# untitled.net
KiCad netlist of a schematic drawn in EAGLE
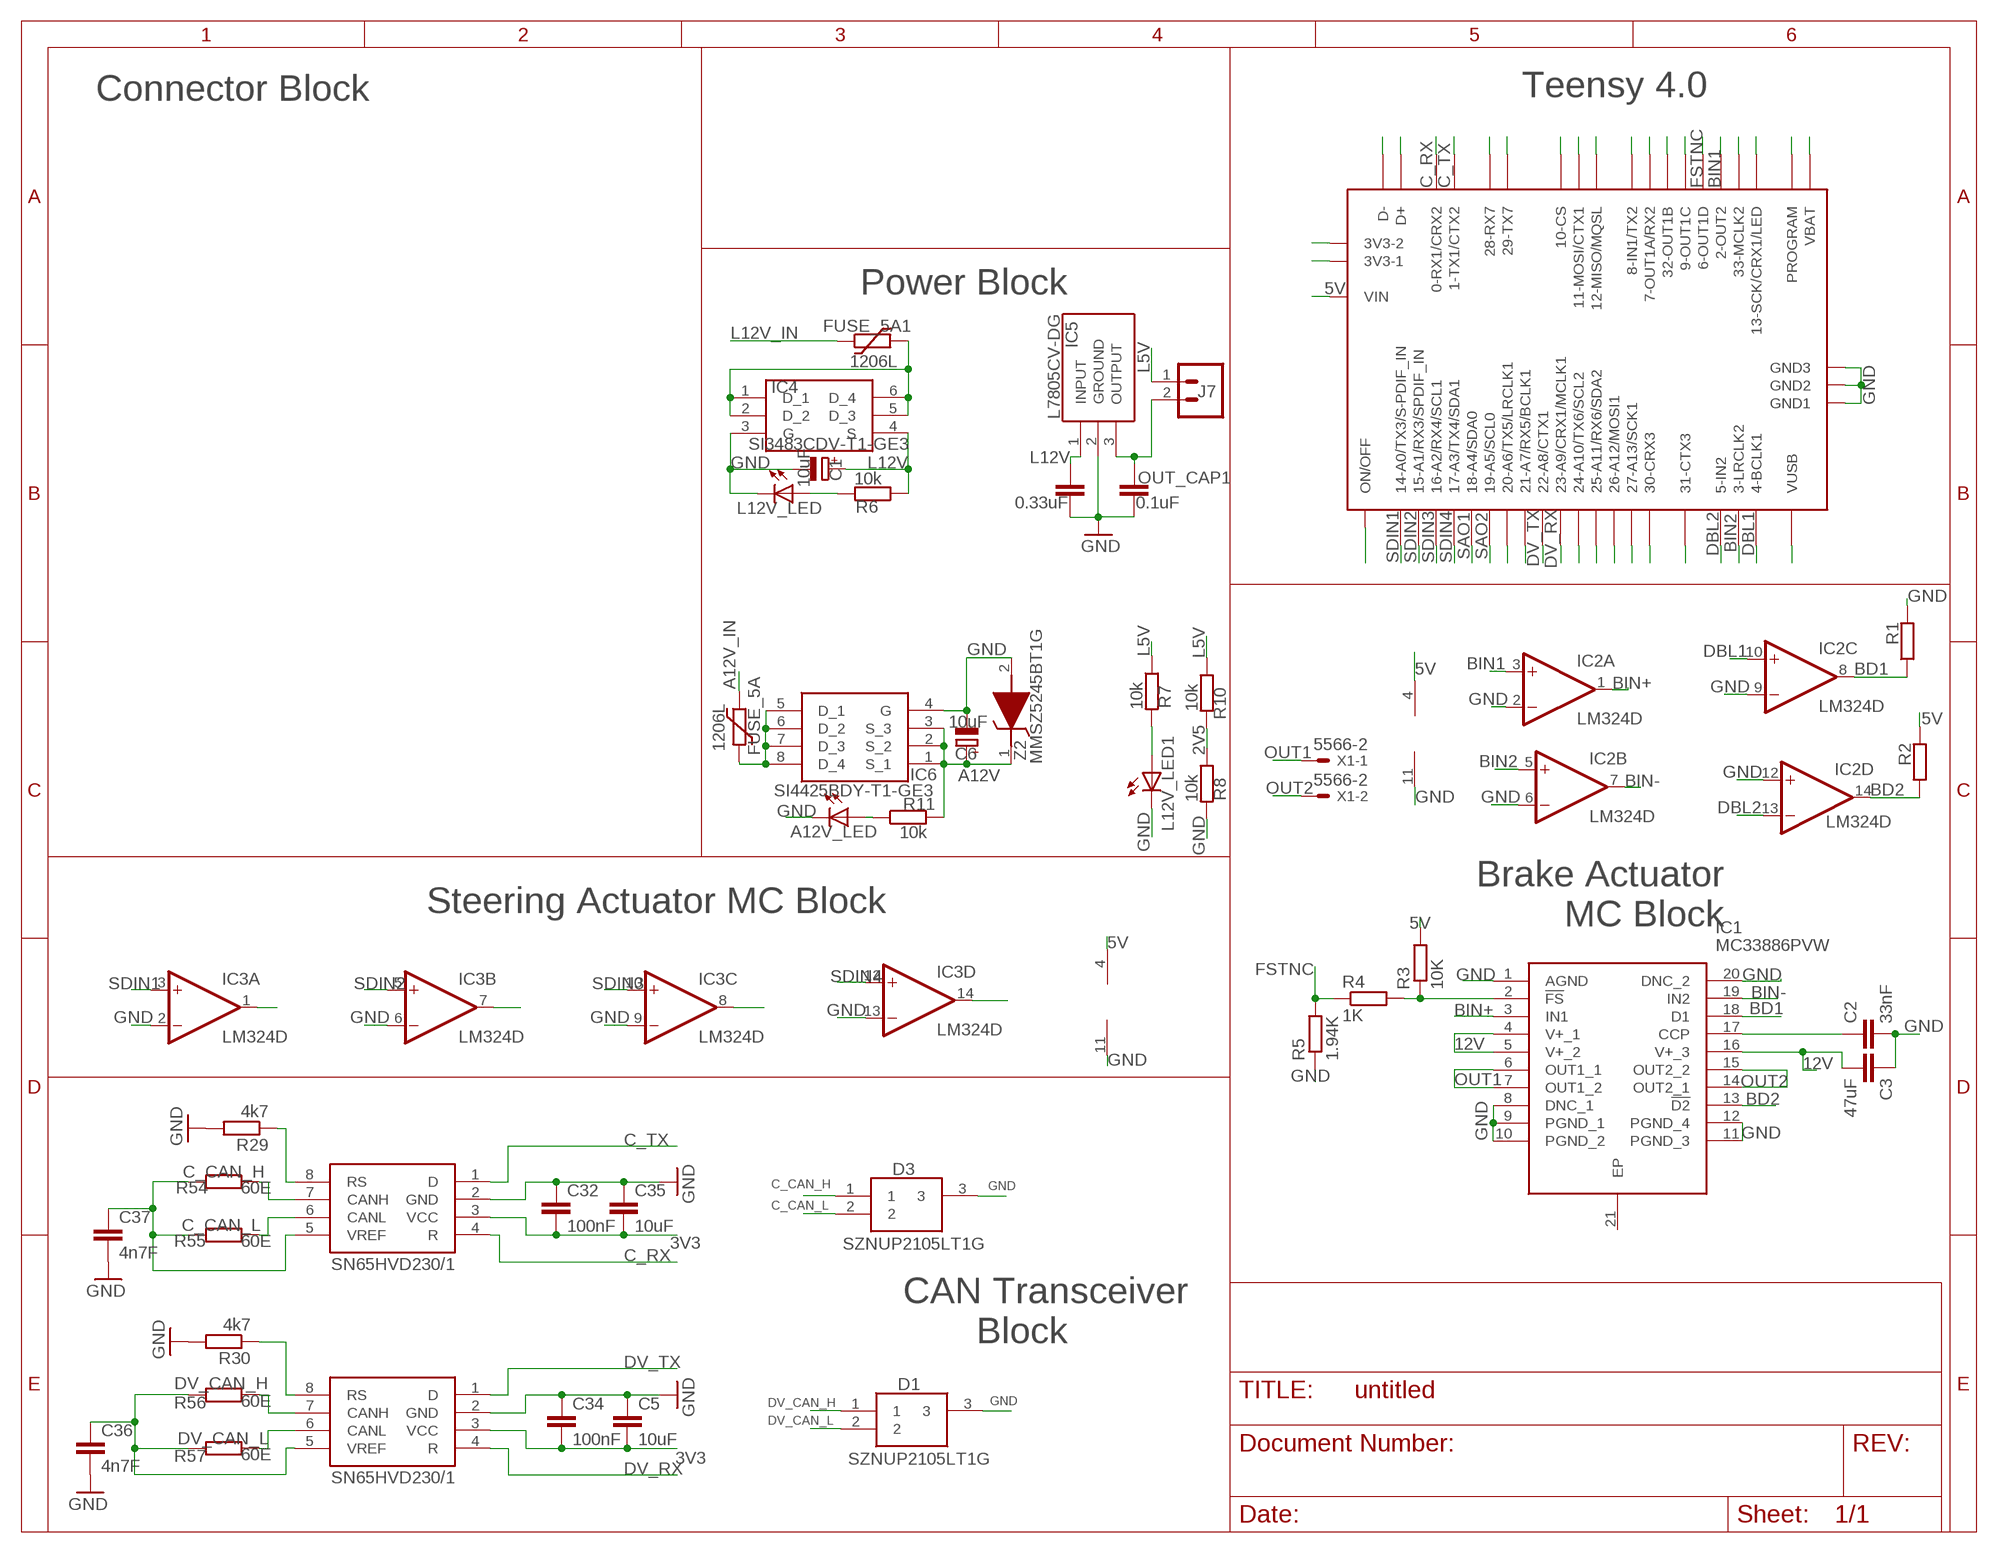
[diagram p0: schematic, sheet 1]

(export (version "E")
  (design (tool "Eeschema 10.0.6"))
  (components
    (comp (ref "A12V_LED")
      (value "LED1206")
      (footprint "eagle-import:LED-1206")
      (libsource (lib "eagle-import") (part "LED1206"))
    )
    (comp (ref "C1")
      (value "10uF")
      (footprint "eagle-import:E2,5-6")
      (libsource (lib "eagle-import") (part "CPOL-EUE2.5-6"))
    )
    (comp (ref "C2")
      (value "33nF")
      (footprint "eagle-import:C0805")
      (libsource (lib "eagle-import") (part "rcl_334_C-EUC0805"))
    )
    (comp (ref "C3")
      (value "47uF")
      (footprint "eagle-import:C1206")
      (libsource (lib "eagle-import") (part "rcl_334_C-EUC1206"))
    )
    (comp (ref "C5")
      (value "10uF")
      (footprint "eagle-import:C0805")
      (libsource (lib "eagle-import") (part "C-EUC0805"))
    )
    (comp (ref "C6")
      (value "10uF")
      (footprint "eagle-import:E2,5-6")
      (libsource (lib "eagle-import") (part "CPOL-EUE2.5-6"))
    )
    (comp (ref "C32")
      (value "100nF")
      (footprint "eagle-import:C0805")
      (libsource (lib "eagle-import") (part "C-EUC0805"))
    )
    (comp (ref "C34")
      (value "100nF")
      (footprint "eagle-import:C0805")
      (libsource (lib "eagle-import") (part "C-EUC0805"))
    )
    (comp (ref "C35")
      (value "10uF")
      (footprint "eagle-import:C0805")
      (libsource (lib "eagle-import") (part "C-EUC0805"))
    )
    (comp (ref "C36")
      (value "4n7F")
      (footprint "eagle-import:C0805")
      (libsource (lib "eagle-import") (part "C-EUC0805"))
    )
    (comp (ref "C37")
      (value "4n7F")
      (footprint "eagle-import:C0805")
      (libsource (lib "eagle-import") (part "C-EUC0805"))
    )
    (comp (ref "D1")
      (value "SZNUP2105LT1G")
      (footprint "eagle-import:SOT96P237X111-3N")
      (fields (field (name "MOUSER_PART_NUMBER") "863-SZNUP2105LT1G"))
      (libsource (lib "eagle-import") (part "SZNUP2105LT1G"))
    )
    (comp (ref "D3")
      (value "SZNUP2105LT1G")
      (footprint "eagle-import:SOT96P237X111-3N")
      (fields (field (name "MOUSER_PART_NUMBER") "863-SZNUP2105LT1G"))
      (libsource (lib "eagle-import") (part "SZNUP2105LT1G"))
    )
    (comp (ref "FUSE_5A")
      (value "1206L")
      (footprint "eagle-import:1206L")
      (libsource (lib "eagle-import") (part "1206L"))
    )
    (comp (ref "FUSE_5A1")
      (value "1206L")
      (footprint "eagle-import:1206L")
      (libsource (lib "eagle-import") (part "1206L"))
    )
    (comp (ref "IC1")
      (value "MC33886PVW")
      (footprint "eagle-import:SOIC127P1420X340-21N")
      (fields (field (name "MOUSER_PART_NUMBER") "841-MC33886PVW"))
      (libsource (lib "eagle-import") (part "MC33886PVW"))
    )
    (comp (ref "IC2")
      (value "LM324D")
      (footprint "eagle-import:SO14")
      (libsource (lib "eagle-import") (part "LM324D"))
    )
    (comp (ref "IC3")
      (value "LM324D")
      (footprint "eagle-import:SO14")
      (libsource (lib "eagle-import") (part "LM324D"))
    )
    (comp (ref "IC4")
      (value "SI3483CDV-T1-GE3")
      (footprint "eagle-import:SOP95P284X110-6N")
      (fields (field (name "MOUSER_PART_NUMBER") "781-SI3483CDV-GE3"))
      (libsource (lib "eagle-import") (part "SI3483CDV-T1-GE3"))
    )
    (comp (ref "IC5")
      (value "L7805CV-DG")
      (footprint "eagle-import:TO255P460X1020X2008-3P")
      (fields (field (name "MOUSER_PART_NUMBER") "511-L7805CV-DG"))
      (libsource (lib "eagle-import") (part "L7805CV-DG"))
    )
    (comp (ref "IC6")
      (value "SI4425BDY-T1-GE3")
      (footprint "eagle-import:SOIC127P600X175-8N")
      (fields (field (name "MOUSER_PART_NUMBER") "781-SI4425BDY-GE3"))
      (libsource (lib "eagle-import") (part "SI4425BDY-T1-GE3"))
    )
    (comp (ref "IN_CAP1")
      (value "0.33uF")
      (footprint "eagle-import:C0805")
      (libsource (lib "eagle-import") (part "C-EUC0805"))
    )
    (comp (ref "J7")
      (value "CONN_02")
      (footprint "eagle-import:1X02")
      (libsource (lib "eagle-import") (part "CONN_02"))
    )
    (comp (ref "L12V_LED")
      (value "LED1206")
      (footprint "eagle-import:LED-1206")
      (libsource (lib "eagle-import") (part "LED1206"))
    )
    (comp (ref "L12V_LED1")
      (value "LED1206")
      (footprint "eagle-import:LED-1206")
      (libsource (lib "eagle-import") (part "LED1206"))
    )
    (comp (ref "OUT_CAP1")
      (value "0.1uF")
      (footprint "eagle-import:C0805")
      (libsource (lib "eagle-import") (part "C-EUC0805"))
    )
    (comp (ref "R1")
      (value "R-EU_R0805")
      (footprint "eagle-import:R0805")
      (libsource (lib "eagle-import") (part "rcl_334_R-EU_R0805"))
    )
    (comp (ref "R2")
      (value "R-EU_R0805")
      (footprint "eagle-import:R0805")
      (libsource (lib "eagle-import") (part "rcl_334_R-EU_R0805"))
    )
    (comp (ref "R3")
      (value "10K")
      (footprint "eagle-import:R0805")
      (libsource (lib "eagle-import") (part "rcl_334_R-EU_R0805"))
    )
    (comp (ref "R4")
      (value "1K")
      (footprint "eagle-import:R0805")
      (libsource (lib "eagle-import") (part "rcl_334_R-EU_R0805"))
    )
    (comp (ref "R5")
      (value "1.94K")
      (footprint "eagle-import:R0805")
      (libsource (lib "eagle-import") (part "rcl_334_R-EU_R0805"))
    )
    (comp (ref "R6")
      (value "10k")
      (footprint "eagle-import:R0805")
      (libsource (lib "eagle-import") (part "R-EU_R0805"))
    )
    (comp (ref "R7")
      (value "10k")
      (footprint "eagle-import:R0805")
      (libsource (lib "eagle-import") (part "R-EU_R0805"))
    )
    (comp (ref "R8")
      (value "10k")
      (footprint "eagle-import:R0805")
      (libsource (lib "eagle-import") (part "R-EU_R0805"))
    )
    (comp (ref "R10")
      (value "10k")
      (footprint "eagle-import:R0805")
      (libsource (lib "eagle-import") (part "R-EU_R0805"))
    )
    (comp (ref "R11")
      (value "10k")
      (footprint "eagle-import:R0805")
      (libsource (lib "eagle-import") (part "R-EU_R0805"))
    )
    (comp (ref "R29")
      (value "4k7")
      (footprint "eagle-import:R0805")
      (libsource (lib "eagle-import") (part "R-EU_R0805"))
    )
    (comp (ref "R30")
      (value "4k7")
      (footprint "eagle-import:R0805")
      (libsource (lib "eagle-import") (part "R-EU_R0805"))
    )
    (comp (ref "R54")
      (value "60E")
      (footprint "eagle-import:R0805")
      (libsource (lib "eagle-import") (part "R-EU_R0805"))
    )
    (comp (ref "R55")
      (value "60E")
      (footprint "eagle-import:R0805")
      (libsource (lib "eagle-import") (part "R-EU_R0805"))
    )
    (comp (ref "R56")
      (value "60E")
      (footprint "eagle-import:R0805")
      (libsource (lib "eagle-import") (part "R-EU_R0805"))
    )
    (comp (ref "R57")
      (value "60E")
      (footprint "eagle-import:R0805")
      (libsource (lib "eagle-import") (part "R-EU_R0805"))
    )
    (comp (ref "U$1")
      (value "TEENSY40")
      (footprint "eagle-import:TEENSY40")
      (libsource (lib "eagle-import") (part "TEENSY40"))
    )
    (comp (ref "U$7")
      (value "SN65HVD230/1")
      (footprint "eagle-import:SO8")
      (libsource (lib "eagle-import") (part "SN65HVD230/1"))
    )
    (comp (ref "U$8")
      (value "SN65HVD230/1")
      (footprint "eagle-import:SO8")
      (libsource (lib "eagle-import") (part "SN65HVD230/1"))
    )
    (comp (ref "X1")
      (value "5566-2")
      (footprint "eagle-import:5566-2")
      (fields (field (name "MF") "MOLEX"))
      (libsource (lib "eagle-import") (part "5566-2"))
    )
    (comp (ref "Z2")
      (value "MMSZ5245BT1G")
      (footprint "eagle-import:SOD3716X135N")
      (fields (field (name "MOUSER_PART_NUMBER") "863-MMSZ5245BT1G"))
      (libsource (lib "eagle-import") (part "MMSZ5245BT1G"))
    )
  )
  (nets
    (net (code "1") (name "/2V5") (class "Default")
      (node (ref "R10") (pin "2") (pinfunction "2_2") (pintype "passive"))
      (node (ref "R8") (pin "1") (pinfunction "1_1") (pintype "passive"))
    )
    (net (code "2") (name "/3V3") (class "Default")
      (node (ref "C32") (pin "2") (pinfunction "2_2") (pintype "passive"))
      (node (ref "C34") (pin "2") (pinfunction "2_2") (pintype "passive"))
      (node (ref "C35") (pin "2") (pinfunction "2_2") (pintype "passive"))
      (node (ref "C5") (pin "2") (pinfunction "2_2") (pintype "passive"))
      (node (ref "U$7") (pin "3") (pinfunction "VCC_3") (pintype "power_in"))
      (node (ref "U$8") (pin "3") (pinfunction "VCC_3") (pintype "power_in"))
    )
    (net (code "3") (name "/5V") (class "Default")
      (node (ref "IC2") (pin "4") (pinfunction "V+_4") (pintype "power_in"))
      (node (ref "IC3") (pin "4") (pinfunction "V+_4") (pintype "power_in"))
      (node (ref "R2") (pin "2") (pinfunction "2_2") (pintype "passive"))
      (node (ref "R3") (pin "2") (pinfunction "2_2") (pintype "passive"))
      (node (ref "U$1") (pin "VIN") (pinfunction "VIN_VIN") (pintype "bidirectional"))
    )
    (net (code "4") (name "/12V") (class "Default")
      (node (ref "C3") (pin "2") (pinfunction "2_2") (pintype "passive"))
      (node (ref "IC1") (pin "16") (pinfunction "V+_3_16") (pintype "bidirectional"))
      (node (ref "IC1") (pin "4") (pinfunction "V+_1_4") (pintype "bidirectional"))
      (node (ref "IC1") (pin "5") (pinfunction "V+_2_5") (pintype "bidirectional"))
    )
    (net (code "5") (name "/A12V") (class "Default")
      (node (ref "C6") (pin "+") (pinfunction "+_+") (pintype "passive"))
      (node (ref "IC6") (pin "1") (pinfunction "S_1_1") (pintype "bidirectional"))
      (node (ref "IC6") (pin "2") (pinfunction "S_2_2") (pintype "bidirectional"))
      (node (ref "IC6") (pin "3") (pinfunction "S_3_3") (pintype "bidirectional"))
      (node (ref "R11") (pin "2") (pinfunction "2_2") (pintype "passive"))
      (node (ref "Z2") (pin "1") (pinfunction "K_1") (pintype "bidirectional"))
    )
    (net (code "6") (name "/A12V_IN") (class "Default")
      (node (ref "FUSE_5A") (pin "P$1") (pinfunction "1_P$1") (pintype "passive"))
    )
    (net (code "7") (name "/BD1") (class "Default")
      (node (ref "IC1") (pin "18") (pinfunction "D1_18") (pintype "bidirectional"))
      (node (ref "IC2") (pin "8") (pinfunction "OUT_8") (pintype "output"))
      (node (ref "R1") (pin "1") (pinfunction "1_1") (pintype "passive"))
    )
    (net (code "8") (name "/BD2") (class "Default")
      (node (ref "IC1") (pin "13") (pinfunction "~{D2}_13") (pintype "bidirectional"))
      (node (ref "IC2") (pin "14") (pinfunction "OUT_14") (pintype "output"))
      (node (ref "R2") (pin "1") (pinfunction "1_1") (pintype "passive"))
    )
    (net (code "9") (name "/BIN+") (class "Default")
      (node (ref "IC1") (pin "3") (pinfunction "IN1_3") (pintype "bidirectional"))
      (node (ref "IC2") (pin "1") (pinfunction "OUT_1") (pintype "output"))
    )
    (net (code "10") (name "/BIN-") (class "Default")
      (node (ref "IC1") (pin "19") (pinfunction "IN2_19") (pintype "bidirectional"))
      (node (ref "IC2") (pin "7") (pinfunction "OUT_7") (pintype "output"))
    )
    (net (code "11") (name "/BIN1") (class "Default")
      (node (ref "IC2") (pin "3") (pinfunction "+IN_3") (pintype "input"))
      (node (ref "U$1") (pin "2-OUT2") (pinfunction "2-OUT2_2-OUT2") (pintype "bidirectional"))
    )
    (net (code "12") (name "/BIN2") (class "Default")
      (node (ref "IC2") (pin "5") (pinfunction "+IN_5") (pintype "input"))
      (node (ref "U$1") (pin "3-LRCLK2") (pinfunction "3-LRCLK2_3-LRCLK2") (pintype "bidirectional"))
    )
    (net (code "13") (name "/C_CAN_H") (class "Default")
      (node (ref "D3") (pin "1") (pinfunction "1_1") (pintype "bidirectional"))
      (node (ref "R54") (pin "1") (pinfunction "1_1") (pintype "passive"))
      (node (ref "U$8") (pin "7") (pinfunction "CANH_7") (pintype "bidirectional"))
    )
    (net (code "14") (name "/C_CAN_L") (class "Default")
      (node (ref "D3") (pin "2") (pinfunction "2_2") (pintype "bidirectional"))
      (node (ref "R55") (pin "1") (pinfunction "1_1") (pintype "passive"))
      (node (ref "U$8") (pin "6") (pinfunction "CANL_6") (pintype "bidirectional"))
    )
    (net (code "15") (name "/C_RX") (class "Default")
      (node (ref "U$1") (pin "0-RX1") (pinfunction "0-RX1/CRX2_0-RX1") (pintype "bidirectional"))
      (node (ref "U$8") (pin "4") (pinfunction "R_4") (pintype "bidirectional"))
    )
    (net (code "16") (name "/C_TX") (class "Default")
      (node (ref "U$1") (pin "1-TX1") (pinfunction "1-TX1/CTX2_1-TX1") (pintype "bidirectional"))
      (node (ref "U$8") (pin "1") (pinfunction "D_1") (pintype "bidirectional"))
    )
    (net (code "17") (name "/DBL1") (class "Default")
      (node (ref "IC2") (pin "10") (pinfunction "+IN_10") (pintype "input"))
      (node (ref "U$1") (pin "4-BCLK2") (pinfunction "4-BCLK1_4-BCLK2") (pintype "bidirectional"))
    )
    (net (code "18") (name "/DBL2") (class "Default")
      (node (ref "IC2") (pin "13") (pinfunction "-IN_13") (pintype "input"))
      (node (ref "U$1") (pin "5-IN2") (pinfunction "5-IN2_5-IN2") (pintype "bidirectional"))
    )
    (net (code "19") (name "/DV_CAN_H") (class "Default")
      (node (ref "D1") (pin "1") (pinfunction "1_1") (pintype "bidirectional"))
      (node (ref "R56") (pin "1") (pinfunction "1_1") (pintype "passive"))
      (node (ref "U$7") (pin "7") (pinfunction "CANH_7") (pintype "bidirectional"))
    )
    (net (code "20") (name "/DV_CAN_L") (class "Default")
      (node (ref "D1") (pin "2") (pinfunction "2_2") (pintype "bidirectional"))
      (node (ref "R57") (pin "1") (pinfunction "1_1") (pintype "passive"))
      (node (ref "U$7") (pin "6") (pinfunction "CANL_6") (pintype "bidirectional"))
    )
    (net (code "21") (name "/DV_RX") (class "Default")
      (node (ref "U$1") (pin "23-A9/CRX1/CCLK1") (pinfunction "23-A9/CRX1/MCLK1_23-A9/CRX1/CCLK1") (pintype "bidirectional"))
      (node (ref "U$7") (pin "4") (pinfunction "R_4") (pintype "bidirectional"))
    )
    (net (code "22") (name "/DV_TX") (class "Default")
      (node (ref "U$1") (pin "22-A8/CTX1") (pinfunction "22-A8/CTX1_22-A8/CTX1") (pintype "bidirectional"))
      (node (ref "U$7") (pin "1") (pinfunction "D_1") (pintype "bidirectional"))
    )
    (net (code "23") (name "/FSTNC") (class "Default")
      (node (ref "R4") (pin "1") (pinfunction "1_1") (pintype "passive"))
      (node (ref "R5") (pin "2") (pinfunction "2_2") (pintype "passive"))
      (node (ref "U$1") (pin "6-OUT1D") (pinfunction "6-OUT1D_6-OUT1D") (pintype "bidirectional"))
    )
    (net (code "24") (name "/L5V") (class "Default")
      (node (ref "J7") (pin "1") (pinfunction "1_1") (pintype "passive"))
      (node (ref "R10") (pin "1") (pinfunction "1_1") (pintype "passive"))
      (node (ref "R7") (pin "1") (pinfunction "1_1") (pintype "passive"))
    )
    (net (code "25") (name "/L12V") (class "Default")
      (node (ref "C1") (pin "+") (pinfunction "+_+") (pintype "passive"))
      (node (ref "IC4") (pin "4") (pinfunction "S_4") (pintype "bidirectional"))
      (node (ref "IC5") (pin "1") (pinfunction "INPUT_1") (pintype "bidirectional"))
      (node (ref "IN_CAP1") (pin "1") (pinfunction "1_1") (pintype "passive"))
      (node (ref "R6") (pin "1") (pinfunction "1_1") (pintype "passive"))
    )
    (net (code "26") (name "/L12V_IN") (class "Default")
      (node (ref "FUSE_5A1") (pin "P$1") (pinfunction "1_P$1") (pintype "passive"))
    )
    (net (code "27") (name "/OUT1") (class "Default")
      (node (ref "IC1") (pin "6") (pinfunction "OUT1_1_6") (pintype "bidirectional"))
      (node (ref "IC1") (pin "7") (pinfunction "OUT1_2_7") (pintype "bidirectional"))
      (node (ref "X1") (pin "1") (pinfunction "S_1") (pintype "passive"))
    )
    (net (code "28") (name "/OUT2") (class "Default")
      (node (ref "IC1") (pin "14") (pinfunction "OUT2_1_14") (pintype "bidirectional"))
      (node (ref "IC1") (pin "15") (pinfunction "OUT2_2_15") (pintype "bidirectional"))
      (node (ref "X1") (pin "2") (pinfunction "S_2") (pintype "passive"))
    )
    (net (code "29") (name "/SAO1") (class "Default")
      (node (ref "U$1") (pin "18-A4/SDA0") (pinfunction "18-A4/SDA0_18-A4/SDA0") (pintype "bidirectional"))
    )
    (net (code "30") (name "/SAO2") (class "Default")
      (node (ref "U$1") (pin "19-A5/SCL0") (pinfunction "19-A5/SCL0_19-A5/SCL0") (pintype "bidirectional"))
    )
    (net (code "31") (name "/SDIN1") (class "Default")
      (node (ref "IC3") (pin "3") (pinfunction "+IN_3") (pintype "input"))
      (node (ref "U$1") (pin "14-A0/TX3/S-PFI_OUT") (pinfunction "14-A0/TX3/S-PDIF_IN_14-A0/TX3/S-PFI_OUT") (pintype "bidirectional"))
    )
    (net (code "32") (name "/SDIN2") (class "Default")
      (node (ref "IC3") (pin "5") (pinfunction "+IN_5") (pintype "input"))
      (node (ref "U$1") (pin "15-A1/RX3/S-PDIF_IN") (pinfunction "15-A1/RX3/SPDIF_IN_15-A1/RX3/S-PDIF_IN") (pintype "bidirectional"))
    )
    (net (code "33") (name "/SDIN3") (class "Default")
      (node (ref "IC3") (pin "10") (pinfunction "+IN_10") (pintype "input"))
      (node (ref "U$1") (pin "16-A2/RX4/SCL1") (pinfunction "16-A2/RX4/SCL1_16-A2/RX4/SCL1") (pintype "bidirectional"))
    )
    (net (code "34") (name "/SDIN4") (class "Default")
      (node (ref "IC3") (pin "12") (pinfunction "+IN_12") (pintype "input"))
      (node (ref "U$1") (pin "17-A3/TX4/SDA1") (pinfunction "17-A3/TX4/SDA1_17-A3/TX4/SDA1") (pintype "bidirectional"))
    )
    (net (code "35") (name "GND") (class "Default")
      (node (ref "A12V_LED") (pin "C") (pinfunction "C_C") (pintype "passive"))
      (node (ref "C1") (pin "-") (pinfunction "-_-") (pintype "passive"))
      (node (ref "C2") (pin "2") (pinfunction "2_2") (pintype "passive"))
      (node (ref "C3") (pin "1") (pinfunction "1_1") (pintype "passive"))
      (node (ref "C32") (pin "1") (pinfunction "1_1") (pintype "passive"))
      (node (ref "C34") (pin "1") (pinfunction "1_1") (pintype "passive"))
      (node (ref "C35") (pin "1") (pinfunction "1_1") (pintype "passive"))
      (node (ref "C36") (pin "2") (pinfunction "2_2") (pintype "passive"))
      (node (ref "C37") (pin "2") (pinfunction "2_2") (pintype "passive"))
      (node (ref "C5") (pin "1") (pinfunction "1_1") (pintype "passive"))
      (node (ref "C6") (pin "-") (pinfunction "-_-") (pintype "passive"))
      (node (ref "D1") (pin "3") (pinfunction "3_3") (pintype "bidirectional"))
      (node (ref "D3") (pin "3") (pinfunction "3_3") (pintype "bidirectional"))
      (node (ref "IC1") (pin "1") (pinfunction "AGND_1") (pintype "bidirectional"))
      (node (ref "IC1") (pin "10") (pinfunction "PGND_2_10") (pintype "bidirectional"))
      (node (ref "IC1") (pin "11") (pinfunction "PGND_3_11") (pintype "bidirectional"))
      (node (ref "IC1") (pin "12") (pinfunction "PGND_4_12") (pintype "bidirectional"))
      (node (ref "IC1") (pin "20") (pinfunction "DNC_2_20") (pintype "bidirectional"))
      (node (ref "IC1") (pin "8") (pinfunction "DNC_1_8") (pintype "bidirectional"))
      (node (ref "IC1") (pin "9") (pinfunction "PGND_1_9") (pintype "bidirectional"))
      (node (ref "IC2") (pin "11") (pinfunction "V-_11") (pintype "power_in"))
      (node (ref "IC2") (pin "12") (pinfunction "+IN_12") (pintype "input"))
      (node (ref "IC2") (pin "2") (pinfunction "-IN_2") (pintype "input"))
      (node (ref "IC2") (pin "6") (pinfunction "-IN_6") (pintype "input"))
      (node (ref "IC2") (pin "9") (pinfunction "-IN_9") (pintype "input"))
      (node (ref "IC3") (pin "11") (pinfunction "V-_11") (pintype "power_in"))
      (node (ref "IC3") (pin "13") (pinfunction "-IN_13") (pintype "input"))
      (node (ref "IC3") (pin "2") (pinfunction "-IN_2") (pintype "input"))
      (node (ref "IC3") (pin "6") (pinfunction "-IN_6") (pintype "input"))
      (node (ref "IC3") (pin "9") (pinfunction "-IN_9") (pintype "input"))
      (node (ref "IC4") (pin "3") (pinfunction "G_3") (pintype "bidirectional"))
      (node (ref "IC5") (pin "2") (pinfunction "GROUND_2") (pintype "bidirectional"))
      (node (ref "IC6") (pin "4") (pinfunction "G_4") (pintype "bidirectional"))
      (node (ref "IN_CAP1") (pin "2") (pinfunction "2_2") (pintype "passive"))
      (node (ref "L12V_LED") (pin "C") (pinfunction "C_C") (pintype "passive"))
      (node (ref "L12V_LED1") (pin "C") (pinfunction "C_C") (pintype "passive"))
      (node (ref "OUT_CAP1") (pin "2") (pinfunction "2_2") (pintype "passive"))
      (node (ref "R1") (pin "2") (pinfunction "2_2") (pintype "passive"))
      (node (ref "R29") (pin "2") (pinfunction "2_2") (pintype "passive"))
      (node (ref "R30") (pin "2") (pinfunction "2_2") (pintype "passive"))
      (node (ref "R5") (pin "1") (pinfunction "1_1") (pintype "passive"))
      (node (ref "R8") (pin "2") (pinfunction "2_2") (pintype "passive"))
      (node (ref "U$1") (pin "GND1") (pinfunction "GND1_GND1") (pintype "bidirectional"))
      (node (ref "U$1") (pin "GND2") (pinfunction "GND2_GND2") (pintype "bidirectional"))
      (node (ref "U$1") (pin "GND3") (pinfunction "GND3_GND3") (pintype "bidirectional"))
      (node (ref "U$7") (pin "2") (pinfunction "GND_2") (pintype "power_in"))
      (node (ref "U$8") (pin "2") (pinfunction "GND_2") (pintype "power_in"))
      (node (ref "Z2") (pin "2") (pinfunction "A_2") (pintype "bidirectional"))
    )
    (net (code "36") (name "Net-(A12V_LED-PadA)") (class "Default")
      (node (ref "A12V_LED") (pin "A") (pinfunction "A_A") (pintype "passive"))
      (node (ref "R11") (pin "1") (pinfunction "1_1") (pintype "passive"))
    )
    (net (code "37") (name "Net-(FUSE_5A-2)") (class "Default")
      (node (ref "FUSE_5A") (pin "P$2") (pinfunction "2_P$2") (pintype "passive"))
      (node (ref "IC6") (pin "5") (pinfunction "D_1_5") (pintype "bidirectional"))
      (node (ref "IC6") (pin "6") (pinfunction "D_2_6") (pintype "bidirectional"))
      (node (ref "IC6") (pin "7") (pinfunction "D_3_7") (pintype "bidirectional"))
      (node (ref "IC6") (pin "8") (pinfunction "D_4_8") (pintype "bidirectional"))
    )
    (net (code "38") (name "Net-(FUSE_5A1-2)") (class "Default")
      (node (ref "FUSE_5A1") (pin "P$2") (pinfunction "2_P$2") (pintype "passive"))
      (node (ref "IC4") (pin "1") (pinfunction "D_1_1") (pintype "bidirectional"))
      (node (ref "IC4") (pin "2") (pinfunction "D_2_2") (pintype "bidirectional"))
      (node (ref "IC4") (pin "5") (pinfunction "D_3_5") (pintype "bidirectional"))
      (node (ref "IC4") (pin "6") (pinfunction "D_4_6") (pintype "bidirectional"))
    )
    (net (code "39") (name "Net-(IC1-CCP)") (class "Default")
      (node (ref "C2") (pin "1") (pinfunction "1_1") (pintype "passive"))
      (node (ref "IC1") (pin "17") (pinfunction "CCP_17") (pintype "bidirectional"))
    )
    (net (code "40") (name "Net-(IC1-~{FS})") (class "Default")
      (node (ref "IC1") (pin "2") (pinfunction "~{FS}_2") (pintype "bidirectional"))
      (node (ref "R3") (pin "1") (pinfunction "1_1") (pintype "passive"))
      (node (ref "R4") (pin "2") (pinfunction "2_2") (pintype "passive"))
    )
    (net (code "41") (name "Net-(IC5-OUTPUT)") (class "Default")
      (node (ref "IC5") (pin "3") (pinfunction "OUTPUT_3") (pintype "bidirectional"))
      (node (ref "J7") (pin "2") (pinfunction "2_2") (pintype "passive"))
      (node (ref "OUT_CAP1") (pin "1") (pinfunction "1_1") (pintype "passive"))
    )
    (net (code "42") (name "Net-(L12V_LED-PadA)") (class "Default")
      (node (ref "L12V_LED") (pin "A") (pinfunction "A_A") (pintype "passive"))
      (node (ref "R6") (pin "2") (pinfunction "2_2") (pintype "passive"))
    )
    (net (code "43") (name "Net-(L12V_LED1-PadA)") (class "Default")
      (node (ref "L12V_LED1") (pin "A") (pinfunction "A_A") (pintype "passive"))
      (node (ref "R7") (pin "2") (pinfunction "2_2") (pintype "passive"))
    )
    (net (code "44") (name "Net-(U$7-RS)") (class "Default")
      (node (ref "R30") (pin "1") (pinfunction "1_1") (pintype "passive"))
      (node (ref "U$7") (pin "8") (pinfunction "RS_8") (pintype "bidirectional"))
    )
    (net (code "45") (name "Net-(U$7-VREF)") (class "Default")
      (node (ref "C36") (pin "1") (pinfunction "1_1") (pintype "passive"))
      (node (ref "R56") (pin "2") (pinfunction "2_2") (pintype "passive"))
      (node (ref "R57") (pin "2") (pinfunction "2_2") (pintype "passive"))
      (node (ref "U$7") (pin "5") (pinfunction "VREF_5") (pintype "bidirectional"))
    )
    (net (code "46") (name "Net-(U$8-RS)") (class "Default")
      (node (ref "R29") (pin "1") (pinfunction "1_1") (pintype "passive"))
      (node (ref "U$8") (pin "8") (pinfunction "RS_8") (pintype "bidirectional"))
    )
    (net (code "47") (name "Net-(U$8-VREF)") (class "Default")
      (node (ref "C37") (pin "1") (pinfunction "1_1") (pintype "passive"))
      (node (ref "R54") (pin "2") (pinfunction "2_2") (pintype "passive"))
      (node (ref "R55") (pin "2") (pinfunction "2_2") (pintype "passive"))
      (node (ref "U$8") (pin "5") (pinfunction "VREF_5") (pintype "bidirectional"))
    )
    (net (code "48") (name "unconnected-(IC1-EP-Pad21)") (class "Default")
      (node (ref "IC1") (pin "21") (pinfunction "EP_21") (pintype "bidirectional"))
    )
    (net (code "49") (name "unconnected-(IC3A-OUT-Pad1)") (class "Default")
      (node (ref "IC3") (pin "1") (pinfunction "OUT_1") (pintype "output"))
    )
    (net (code "50") (name "unconnected-(IC3B-OUT-Pad7)") (class "Default")
      (node (ref "IC3") (pin "7") (pinfunction "OUT_7") (pintype "output"))
    )
    (net (code "51") (name "unconnected-(IC3C-OUT-Pad8)") (class "Default")
      (node (ref "IC3") (pin "8") (pinfunction "OUT_8") (pintype "output"))
    )
    (net (code "52") (name "unconnected-(IC3D-OUT-Pad14)") (class "Default")
      (node (ref "IC3") (pin "14") (pinfunction "OUT_14") (pintype "output"))
    )
    (net (code "53") (name "unconnected-(U$1-7-OUT1A{slash}RX2-Pad7-RX2{slash}OUT1A)") (class "Default")
      (node (ref "U$1") (pin "7-RX2/OUT1A") (pinfunction "7-OUT1A/RX2_7-RX2/OUT1A") (pintype "bidirectional"))
    )
    (net (code "54") (name "unconnected-(U$1-8-IN1{slash}TX2-Pad8-TX2{slash}IN1)") (class "Default")
      (node (ref "U$1") (pin "8-TX2/IN1") (pinfunction "8-IN1/TX2_8-TX2/IN1") (pintype "bidirectional"))
    )
    (net (code "55") (name "unconnected-(U$1-10-CS-Pad10-CS{slash}MQSR)") (class "Default")
      (node (ref "U$1") (pin "10-CS/MQSR") (pinfunction "10-CS_10-CS/MQSR") (pintype "bidirectional"))
    )
    (net (code "56") (name "unconnected-(U$1-12-MISO{slash}MQSL-Pad12-MIO{slash}MQSL)") (class "Default")
      (node (ref "U$1") (pin "12-MIO/MQSL") (pinfunction "12-MISO/MQSL_12-MIO/MQSL") (pintype "bidirectional"))
    )
    (net (code "57") (name "unconnected-(U$1-25-A11{slash}RX6{slash}SDA2-Pad25-A11{slash}SDA2)") (class "Default")
      (node (ref "U$1") (pin "25-A11/SDA2") (pinfunction "25-A11/RX6/SDA2_25-A11/SDA2") (pintype "bidirectional"))
    )
    (net (code "58") (name "unconnected-(U$1-32-OUT1B-Pad32-OUTB1)") (class "Default")
      (node (ref "U$1") (pin "32-OUTB1") (pinfunction "32-OUT1B_32-OUTB1") (pintype "bidirectional"))
    )
    (net (code "59") (name "unconnected-(U$1-Pad3V3-1)") (class "Default")
      (node (ref "U$1") (pin "3V3-1") (pinfunction "3V3-1_3V3-1") (pintype "bidirectional"))
    )
    (net (code "60") (name "unconnected-(U$1-Pad3V3-2)") (class "Default")
      (node (ref "U$1") (pin "3V3-2") (pinfunction "3V3-2_3V3-2") (pintype "bidirectional"))
    )
    (net (code "61") (name "unconnected-(U$1-Pad9-OUT1C)") (class "Default")
      (node (ref "U$1") (pin "9-OUT1C") (pinfunction "9-OUT1C_9-OUT1C") (pintype "bidirectional"))
    )
    (net (code "62") (name "unconnected-(U$1-Pad11-MOSI{slash}CTX1)") (class "Default")
      (node (ref "U$1") (pin "11-MOSI/CTX1") (pinfunction "11-MOSI/CTX1_11-MOSI/CTX1") (pintype "bidirectional"))
    )
    (net (code "63") (name "unconnected-(U$1-Pad13-SCK{slash}CRX1{slash}LED)") (class "Default")
      (node (ref "U$1") (pin "13-SCK/CRX1/LED") (pinfunction "13-SCK/CRX1/LED_13-SCK/CRX1/LED") (pintype "bidirectional"))
    )
    (net (code "64") (name "unconnected-(U$1-Pad20-A6{slash}TX5{slash}LRCLK1)") (class "Default")
      (node (ref "U$1") (pin "20-A6/TX5/LRCLK1") (pinfunction "20-A6/TX5/LRCLK1_20-A6/TX5/LRCLK1") (pintype "bidirectional"))
    )
    (net (code "65") (name "unconnected-(U$1-Pad21-A7{slash}RX5{slash}BCLK1)") (class "Default")
      (node (ref "U$1") (pin "21-A7/RX5/BCLK1") (pinfunction "21-A7/RX5/BCLK1_21-A7/RX5/BCLK1") (pintype "bidirectional"))
    )
    (net (code "66") (name "unconnected-(U$1-Pad24-A10{slash}TX6{slash}SCL2)") (class "Default")
      (node (ref "U$1") (pin "24-A10/TX6/SCL2") (pinfunction "24-A10/TX6/SCL2_24-A10/TX6/SCL2") (pintype "bidirectional"))
    )
    (net (code "67") (name "unconnected-(U$1-Pad26-A12{slash}MOSI1)") (class "Default")
      (node (ref "U$1") (pin "26-A12/MOSI1") (pinfunction "26-A12/MOSI1_26-A12/MOSI1") (pintype "bidirectional"))
    )
    (net (code "68") (name "unconnected-(U$1-Pad27-A13{slash}SCK1)") (class "Default")
      (node (ref "U$1") (pin "27-A13/SCK1") (pinfunction "27-A13/SCK1_27-A13/SCK1") (pintype "bidirectional"))
    )
    (net (code "69") (name "unconnected-(U$1-Pad28-RX7)") (class "Default")
      (node (ref "U$1") (pin "28-RX7") (pinfunction "28-RX7_28-RX7") (pintype "bidirectional"))
    )
    (net (code "70") (name "unconnected-(U$1-Pad29-TX7)") (class "Default")
      (node (ref "U$1") (pin "29-TX7") (pinfunction "29-TX7_29-TX7") (pintype "bidirectional"))
    )
    (net (code "71") (name "unconnected-(U$1-Pad30-CRX3)") (class "Default")
      (node (ref "U$1") (pin "30-CRX3") (pinfunction "30-CRX3_30-CRX3") (pintype "bidirectional"))
    )
    (net (code "72") (name "unconnected-(U$1-Pad31-CTX3)") (class "Default")
      (node (ref "U$1") (pin "31-CTX3") (pinfunction "31-CTX3_31-CTX3") (pintype "bidirectional"))
    )
    (net (code "73") (name "unconnected-(U$1-Pad33-MCLK2)") (class "Default")
      (node (ref "U$1") (pin "33-MCLK2") (pinfunction "33-MCLK2_33-MCLK2") (pintype "bidirectional"))
    )
    (net (code "74") (name "unconnected-(U$1-PadD+)") (class "Default")
      (node (ref "U$1") (pin "D+") (pinfunction "D+_D+") (pintype "bidirectional"))
    )
    (net (code "75") (name "unconnected-(U$1-PadD-)") (class "Default")
      (node (ref "U$1") (pin "D-") (pinfunction "D-_D-") (pintype "bidirectional"))
    )
    (net (code "76") (name "unconnected-(U$1-PadON{slash}OFF)") (class "Default")
      (node (ref "U$1") (pin "ON/OFF") (pinfunction "ON/OFF_ON/OFF") (pintype "bidirectional"))
    )
    (net (code "77") (name "unconnected-(U$1-PadPROGRAM)") (class "Default")
      (node (ref "U$1") (pin "PROGRAM") (pinfunction "PROGRAM_PROGRAM") (pintype "bidirectional"))
    )
    (net (code "78") (name "unconnected-(U$1-PadVBAT)") (class "Default")
      (node (ref "U$1") (pin "VBAT") (pinfunction "VBAT_VBAT") (pintype "bidirectional"))
    )
    (net (code "79") (name "unconnected-(U$1-PadVUSB)") (class "Default")
      (node (ref "U$1") (pin "VUSB") (pinfunction "VUSB_VUSB") (pintype "bidirectional"))
    )
  )
)
